# KamiGen2.net
KiCad netlist of a schematic drawn in Altium Designer
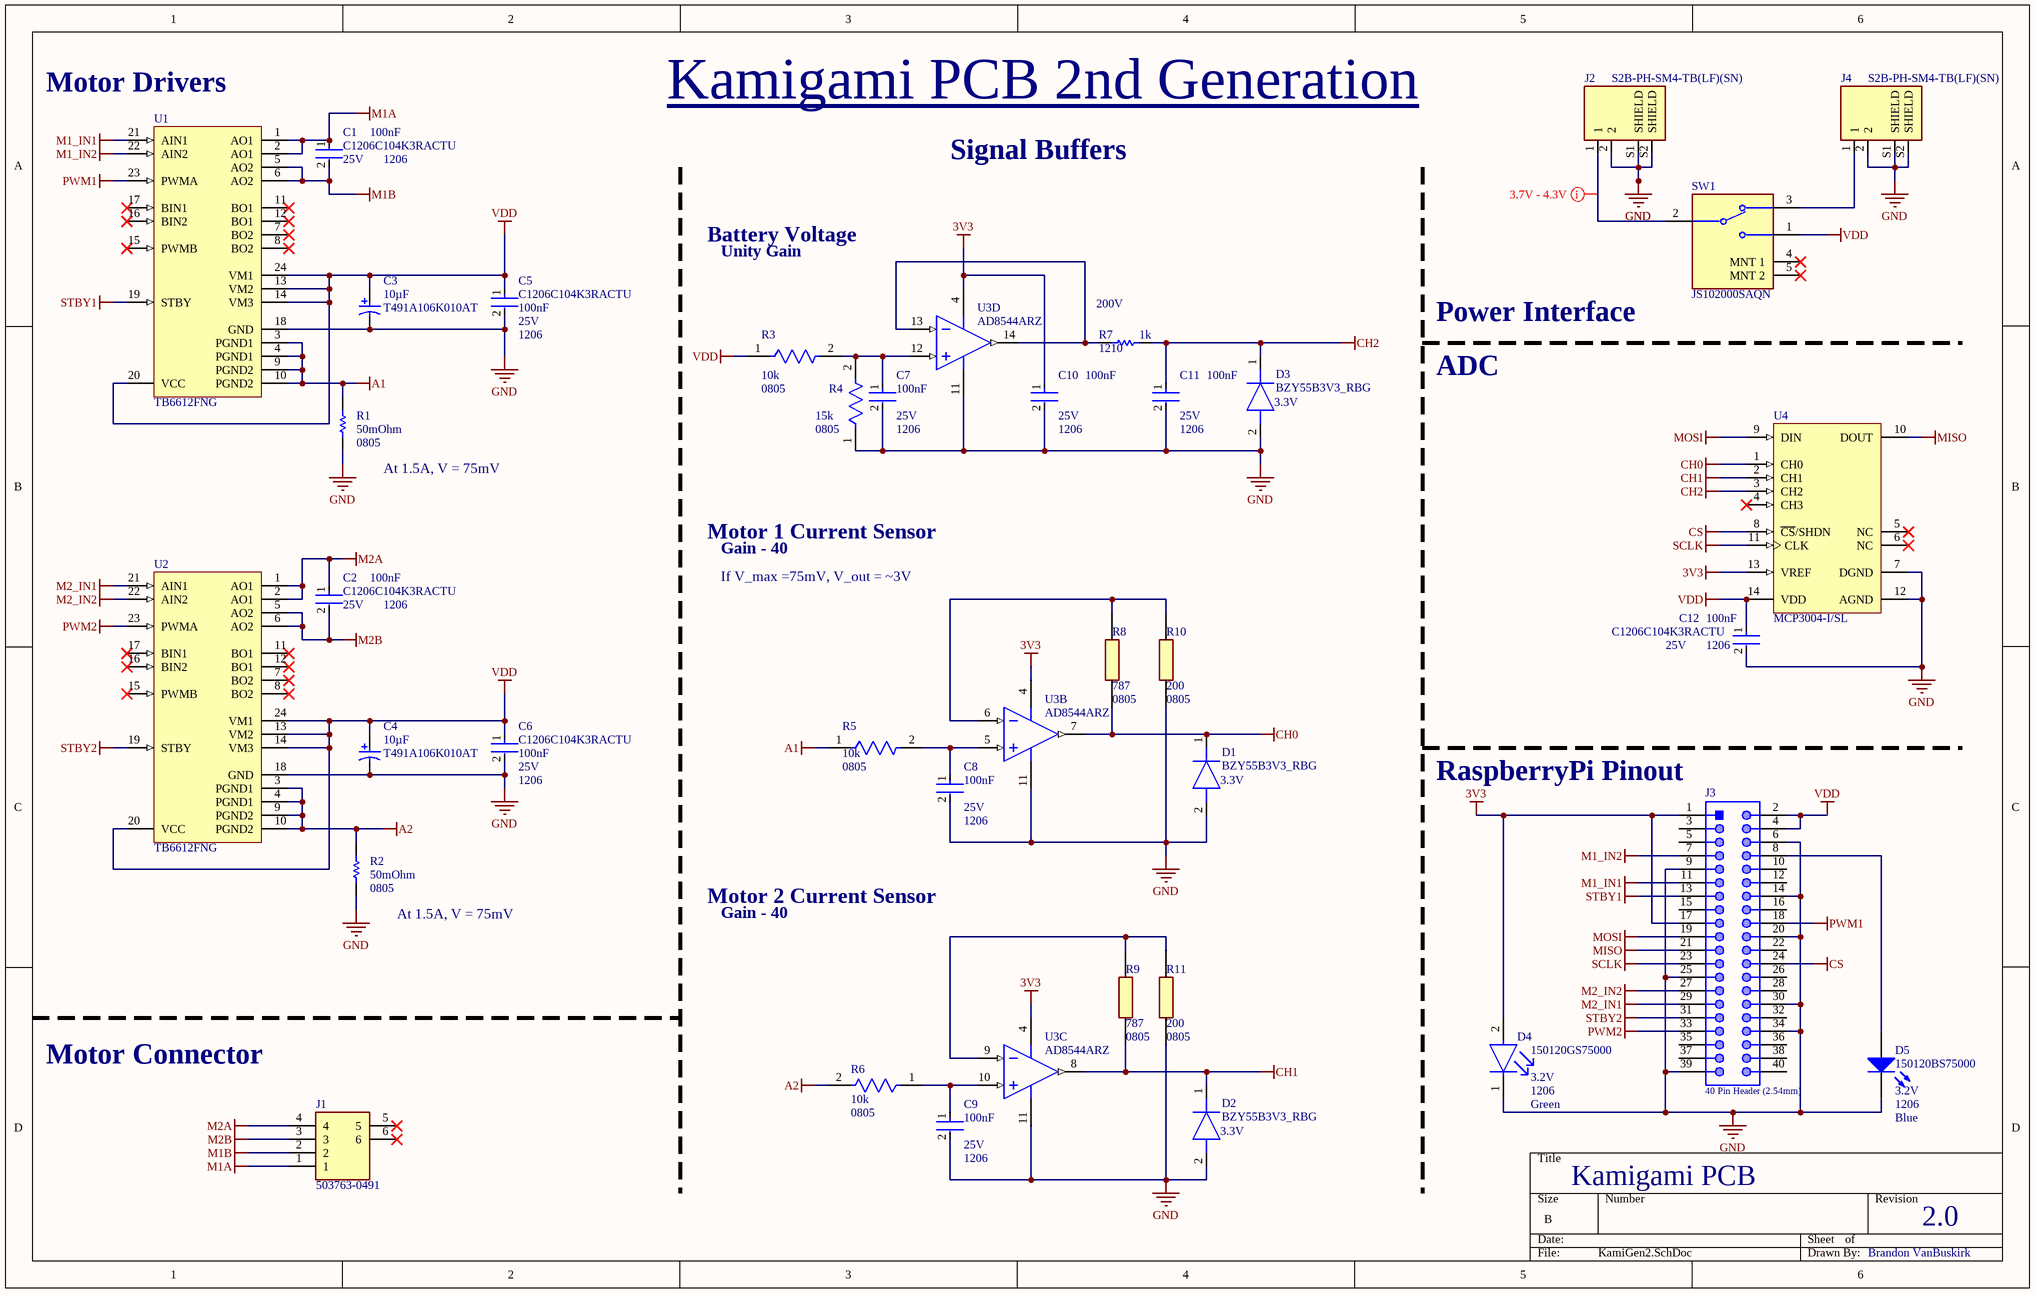
[diagram p0: KamiGen2.SchDoc]

(export (version "E")
  (design (tool "Eeschema 10.0.6"))
  (components
    (comp (ref "C1")
      (value "C1206C104K3RACTU")
      (footprint "FP-C1206C-EB-MFG")
      (description "CAP CER 0.1UF 25V 10% X7R 1206")
      (fields
        (field (name "ALTIUM_VALUE") "100nF")
        (field (name "VOLTAGE RATING (DC)") "25V")
        (field (name "TOLERANCE") "10%")
        (field (name "CASE CODE (IMPERIAL)") "1206")
      )
      (libsource (lib "Verdant Robotics") (part "b4654b650e69147ec39a6b967a45e02"))
    )
    (comp (ref "C2")
      (value "C1206C104K3RACTU")
      (footprint "FP-C1206C-EB-MFG")
      (description "CAP CER 0.1UF 25V 10% X7R 1206")
      (fields
        (field (name "ALTIUM_VALUE") "100nF")
        (field (name "VOLTAGE RATING (DC)") "25V")
        (field (name "TOLERANCE") "10%")
        (field (name "CASE CODE (IMPERIAL)") "1206")
      )
      (libsource (lib "Verdant Robotics") (part "b4654b650e69147ec39a6b967a45e02"))
    )
    (comp (ref "C3")
      (value "T491A106K010AT")
      (footprint "KEMT-A-3216-18-2_M")
      (description "Capacitor, Tantalum, 10 uF, +/- 10%, 10 V, -55 to 125 degC, 2-Pin SMD (1206), RoHS, Tape and Reel")
      (fields
        (field (name "TOLERANCE") "±10%")
        (field (name "MANUFACTURER") "Kemet")
        (field (name "CAPACITANCE") "10µF")
      )
      (libsource (lib "Altium Content Vault") (part "CAP-P-2"))
    )
    (comp (ref "C4")
      (value "T491A106K010AT")
      (footprint "KEMT-A-3216-18-2_M")
      (description "Capacitor, Tantalum, 10 uF, +/- 10%, 10 V, -55 to 125 degC, 2-Pin SMD (1206), RoHS, Tape and Reel")
      (fields
        (field (name "TOLERANCE") "±10%")
        (field (name "MANUFACTURER") "Kemet")
        (field (name "CAPACITANCE") "10µF")
      )
      (libsource (lib "Altium Content Vault") (part "CAP-P-2"))
    )
    (comp (ref "C5")
      (value "C1206C104K3RACTU")
      (footprint "FP-C1206C-EB-MFG")
      (description "CAP CER 0.1UF 25V 10% X7R 1206")
      (fields
        (field (name "ALTIUM_VALUE") "100nF")
        (field (name "VOLTAGE RATING (DC)") "25V")
        (field (name "TOLERANCE") "10%")
        (field (name "CASE CODE (IMPERIAL)") "1206")
      )
      (libsource (lib "Verdant Robotics") (part "b4654b650e69147ec39a6b967a45e02"))
    )
    (comp (ref "C6")
      (value "C1206C104K3RACTU")
      (footprint "FP-C1206C-EB-MFG")
      (description "CAP CER 0.1UF 25V 10% X7R 1206")
      (fields
        (field (name "ALTIUM_VALUE") "100nF")
        (field (name "VOLTAGE RATING (DC)") "25V")
        (field (name "TOLERANCE") "10%")
        (field (name "CASE CODE (IMPERIAL)") "1206")
      )
      (libsource (lib "Verdant Robotics") (part "b4654b650e69147ec39a6b967a45e02"))
    )
    (comp (ref "C7")
      (value "100nF")
      (footprint "FP-C1206C-EB-MFG")
      (description "CAP CER 0.1UF 25V 10% X7R 1206")
      (fields
        (field (name "VOLTAGE RATING (DC)") "25V")
        (field (name "TOLERANCE") "10%")
        (field (name "CASE CODE (IMPERIAL)") "1206")
        (field (name "Comment") "C1206C104K3RACTU")
      )
      (libsource (lib "Verdant Robotics") (part "b4654b650e69147ec39a6b967a45e02"))
    )
    (comp (ref "C8")
      (value "100nF")
      (footprint "FP-C1206C-EB-MFG")
      (description "CAP CER 0.1UF 25V 10% X7R 1206")
      (fields
        (field (name "VOLTAGE RATING (DC)") "25V")
        (field (name "TOLERANCE") "10%")
        (field (name "CASE CODE (IMPERIAL)") "1206")
        (field (name "Comment") "C1206C104K3RACTU")
      )
      (libsource (lib "Verdant Robotics") (part "b4654b650e69147ec39a6b967a45e02"))
    )
    (comp (ref "C9")
      (value "100nF")
      (footprint "FP-C1206C-EB-MFG")
      (description "CAP CER 0.1UF 25V 10% X7R 1206")
      (fields
        (field (name "VOLTAGE RATING (DC)") "25V")
        (field (name "TOLERANCE") "10%")
        (field (name "CASE CODE (IMPERIAL)") "1206")
        (field (name "Comment") "C1206C104K3RACTU")
      )
      (libsource (lib "Verdant Robotics") (part "b4654b650e69147ec39a6b967a45e02"))
    )
    (comp (ref "C10")
      (value "100nF")
      (footprint "FP-C1206C-EB-MFG")
      (description "CAP CER 0.1UF 25V 10% X7R 1206")
      (fields
        (field (name "VOLTAGE RATING (DC)") "25V")
        (field (name "TOLERANCE") "10%")
        (field (name "CASE CODE (IMPERIAL)") "1206")
        (field (name "Comment") "C1206C104K3RACTU")
      )
      (libsource (lib "Verdant Robotics") (part "b4654b650e69147ec39a6b967a45e02"))
    )
    (comp (ref "C11")
      (value "100nF")
      (footprint "FP-C1206C-EB-MFG")
      (description "CAP CER 0.1UF 25V 10% X7R 1206")
      (fields
        (field (name "VOLTAGE RATING (DC)") "25V")
        (field (name "TOLERANCE") "10%")
        (field (name "CASE CODE (IMPERIAL)") "1206")
        (field (name "Comment") "C1206C104K3RACTU")
      )
      (libsource (lib "Verdant Robotics") (part "b4654b650e69147ec39a6b967a45e02"))
    )
    (comp (ref "C12")
      (value "C1206C104K3RACTU")
      (footprint "FP-C1206C-EB-MFG")
      (description "CAP CER 0.1UF 25V 10% X7R 1206")
      (fields
        (field (name "ALTIUM_VALUE") "100nF")
        (field (name "VOLTAGE RATING (DC)") "25V")
        (field (name "TOLERANCE") "10%")
        (field (name "CASE CODE (IMPERIAL)") "1206")
      )
      (libsource (lib "Verdant Robotics") (part "b4654b650e69147ec39a6b967a45e02"))
    )
    (comp (ref "D1")
      (value "BZY55B3V3_RBG")
      (footprint "SamacSys:BZY55B3V3RBG")
      (description "Diode")
      (fields
        (field (name "MANUFACTURER_PART_NUMBER") "BZY55B3V3 RBG")
        (field (name "MOUSER PART NUMBER") "821-BZY55B3V3RBG")
        (field (name "ZENER VOLTAGE") "3.3V")
      )
      (libsource (lib "*") (part "BZY55B3V3_RBG"))
    )
    (comp (ref "D2")
      (value "BZY55B3V3_RBG")
      (footprint "SamacSys:BZY55B3V3RBG")
      (description "Diode")
      (fields
        (field (name "MANUFACTURER_PART_NUMBER") "BZY55B3V3 RBG")
        (field (name "MOUSER PART NUMBER") "821-BZY55B3V3RBG")
        (field (name "ZENER VOLTAGE") "3.3V")
      )
      (libsource (lib "*") (part "BZY55B3V3_RBG"))
    )
    (comp (ref "D3")
      (value "BZY55B3V3_RBG")
      (footprint "SamacSys:BZY55B3V3RBG")
      (description "Diode")
      (fields
        (field (name "MANUFACTURER_PART_NUMBER") "BZY55B3V3 RBG")
        (field (name "MOUSER PART NUMBER") "821-BZY55B3V3RBG")
        (field (name "ZENER VOLTAGE") "3.3V")
      )
      (libsource (lib "*") (part "BZY55B3V3_RBG"))
    )
    (comp (ref "D4")
      (value "150120GS75000")
      (footprint "FP-150120GS75000-MFG")
      (description "LED GREEN CLEAR 1206 SMD")
      (fields
        (field (name "COLOR") "Green")
        (field (name "CASE/PACKAGE") "1206")
        (field (name "FORWARD VOLTAGE") "3.2V")
      )
      (libsource (lib "Altium Content Vault") (part "8706943c75ba83719d021d2fdc84c58"))
    )
    (comp (ref "D5")
      (value "150120BS75000")
      (footprint "1206_A")
      (description "SMD mono-color Chip LED, WL-SMCW, Blue")
      (fields
        (field (name "MANUFACTURER") "Wuerth Elektronik")
        (field (name "PACKAGEREFERENCE") "1206")
        (field (name "COLOR") "Blue")
        (field (name "FORWARD VOLTAGE") "3.2V")
      )
      (libsource (lib "Altium Content Vault") (part "WE-LED_K1A2-2"))
    )
    (comp (ref "J1")
      (value "503763-0491")
      (footprint "SamacSys:5037630491")
      (description "Connector")
      (fields (field (name "MOUSER PART NUMBER") "538-503763-0491"))
      (libsource (lib "*") (part "503763-0491"))
    )
    (comp (ref "J2")
      (value "S2B-PH-SM4-TB(LF)(SN)")
      (footprint "JST_S2B-PH-SM4-TB(LF)(SN)")
      (description "Connector Header Surface Mount, Right Angle 2 position 0.079 (2.00mm)")
      (fields (field (name "DIGI-KEY_PART_NUMBER") "455-1749-2-ND") (field (name "MF") "JST Sales"))
      (libsource (lib "Verdant Robotics") (part "S2B-PH-SM4-TB(LF)(SN)"))
    )
    (comp (ref "J3")
      (value "40 Pin Header (2.54mm)")
      (footprint "61304021121")
      (description "WR-PHD Straight Male, PCB Header, Through Hole, 2 Rows, 40 Contacts, 2.54mm Pitch")
      (libsource (lib "Verdant Robotics") (part "WE-CN-2P-M-R40"))
    )
    (comp (ref "J4")
      (value "S2B-PH-SM4-TB(LF)(SN)")
      (footprint "JST_S2B-PH-SM4-TB(LF)(SN)")
      (description "Connector Header Surface Mount, Right Angle 2 position 0.079 (2.00mm)")
      (fields (field (name "DIGI-KEY_PART_NUMBER") "455-1749-2-ND") (field (name "MF") "JST Sales"))
      (libsource (lib "Verdant Robotics") (part "S2B-PH-SM4-TB(LF)(SN)"))
    )
    (comp (ref "R1")
      (value "WSL0805R0500FEA")
      (footprint "RESC2013X46X38ML25T25")
      (fields
        (field (name "MANUFACTURER") "Vishay Dale")
        (field (name "RESISTANCE") "50mOhm")
        (field (name "CASE") "0805")
      )
      (libsource (lib "Altium Content Vault") (part "RES"))
    )
    (comp (ref "R2")
      (value "WSL0805R0500FEA")
      (footprint "RESC2013X46X38ML25T25")
      (fields
        (field (name "MANUFACTURER") "Vishay Dale")
        (field (name "RESISTANCE") "50mOhm")
        (field (name "CASE") "0805")
      )
      (libsource (lib "Altium Content Vault") (part "RES"))
    )
    (comp (ref "R3")
      (value "CRCW080510K0FKEA")
      (footprint "FP-CRCW0805-e3-IPC_A")
      (description "RES Thick Film, 10kΩ, 1%, 0.125W, 100ppm/°C, 0805")
      (fields
        (field (name "RESISTANCE") "10k")
        (field (name "TOLERANCE") "1%")
        (field (name "CASE/PACKAGE") "0805")
      )
      (libsource (lib "Altium Content Vault") (part "1029c3af85768c4190bb7ad29bc67b5"))
    )
    (comp (ref "R4")
      (value "ERJ-6ENF1502V")
      (footprint "FP-ERJ6EN-IPC_C")
      (description "RES SMD 15K OHM 1% 1/8W 0805")
      (fields
        (field (name "CASE/PACKAGE") "0805")
        (field (name "TOLERANCE") "1%")
        (field (name "RESISTANCE") "15k")
      )
      (libsource (lib "Altium Content Vault") (part "8db39607336c341a927600551d01821"))
    )
    (comp (ref "R5")
      (value "CRCW080510K0FKEA")
      (footprint "FP-CRCW0805-e3-IPC_A")
      (description "RES Thick Film, 10kΩ, 1%, 0.125W, 100ppm/°C, 0805")
      (fields
        (field (name "RESISTANCE") "10k")
        (field (name "TOLERANCE") "1%")
        (field (name "CASE/PACKAGE") "0805")
      )
      (libsource (lib "Altium Content Vault") (part "1029c3af85768c4190bb7ad29bc67b5"))
    )
    (comp (ref "R6")
      (value "CRCW080510K0FKEA")
      (footprint "FP-CRCW0805-e3-IPC_A")
      (description "RES Thick Film, 10kΩ, 1%, 0.125W, 100ppm/°C, 0805")
      (fields
        (field (name "RESISTANCE") "10k")
        (field (name "TOLERANCE") "1%")
        (field (name "CASE/PACKAGE") "0805")
      )
      (libsource (lib "Altium Content Vault") (part "1029c3af85768c4190bb7ad29bc67b5"))
    )
    (comp (ref "R7")
      (value "1k")
      (footprint "RESC3225X70X50LL20T20")
      (description "Res Thick Film 1210 1K Ohm 1% 1/2W ±100ppm/°C Molded SMD Embossed Carrier T/R")
      (fields
        (field (name "CASE CODE (IMPERIAL)") "1210")
        (field (name "TOLERANCE") "1%")
        (field (name "VOLTAGE RATING (DC)") "200V")
        (field (name "Comment") "ERJ-14NF1001U")
      )
      (libsource (lib "Verdant Robotics") (part "RES"))
    )
    (comp (ref "R8")
      (value "CRGH0805F787R")
      (footprint "SamacSys:RESC2013X65N")
      (description "Resistor")
      (fields
        (field (name "MOUSER PART NUMBER") "279-CRGH0805F787R")
        (field (name "RESISTANCE") "787")
        (field (name "CASE") "0805")
      )
      (libsource (lib "*") (part "CRGH0805F787R"))
    )
    (comp (ref "R9")
      (value "CRGH0805F787R")
      (footprint "SamacSys:RESC2013X65N")
      (description "Resistor")
      (fields
        (field (name "MOUSER PART NUMBER") "279-CRGH0805F787R")
        (field (name "RESISTANCE") "787")
        (field (name "CASE") "0805")
      )
      (libsource (lib "*") (part "CRGH0805F787R"))
    )
    (comp (ref "R10")
      (value "ERJ-6RBD2000V")
      (footprint "SamacSys:RESC2012X70N")
      (description "Resistor")
      (fields
        (field (name "MOUSER PART NUMBER") "667-ERJ-6RBD2000V")
        (field (name "RESISTANCE") "200")
        (field (name "CASE") "0805")
      )
      (libsource (lib "*") (part "ERJ-6RBD2000V"))
    )
    (comp (ref "R11")
      (value "ERJ-6RBD2000V")
      (footprint "SamacSys:RESC2012X70N")
      (description "Resistor")
      (fields
        (field (name "MOUSER PART NUMBER") "667-ERJ-6RBD2000V")
        (field (name "RESISTANCE") "200")
        (field (name "CASE") "0805")
      )
      (libsource (lib "*") (part "ERJ-6RBD2000V"))
    )
    (comp (ref "SW1")
      (value "JS102000SAQN")
      (footprint "FP-JS102000SAQN-MFG")
      (description "Slide Switch, Js Series, SPDT, Right Angle, SMD, 1 ma Rohs Compliant: Yes")
      (libsource (lib "Verdant Robotics") (part "6887e5fe807d9c5c2853bed39bc55bf"))
    )
    (comp (ref "U1")
      (value "TB6612FNG")
      (footprint "TOSH-SSOP-24_M")
      (description "Driver IC for Dual DC Motor, 15 V, -20 to 85 degC, 24-Pin SSOP, RoHS, Tape and Reel")
      (libsource (lib "Altium Content Vault") (part "TOSH-TB6612FNG-SOP-24"))
    )
    (comp (ref "U2")
      (value "TB6612FNG")
      (footprint "TOSH-SSOP-24_M")
      (description "Driver IC for Dual DC Motor, 15 V, -20 to 85 degC, 24-Pin SSOP, RoHS, Tape and Reel")
      (libsource (lib "Altium Content Vault") (part "TOSH-TB6612FNG-SOP-24"))
    )
    (comp (ref "U3")
      (value "AD8544ARZ")
      (footprint "ADI-R-14_M")
      (description "Operational Amplifier, Quad, 1 Mhz, 4, 0.92 V/ S, 2.7V To 5.5V, Soic, 14 Rohs Compliant: Yes")
      (libsource (lib "Verdant Robotics") (part "ADI-ADxxxx_OPxxxx-X-14"))
    )
    (comp (ref "U4")
      (value "MCP3004-I/SL")
      (footprint "SOIC-SL14_L")
      (description "4-Channel Single ADC SAR 200ksps 10-bit Serial Automotive 14-Pin SOIC N Tube")
      (libsource (lib "Verdant Robotics") (part "CON-ADC-MCP3004-14"))
    )
  )
  (nets
    (net (code "1") (name "3V3") (class "Default")
      (node (ref "C10") (pin "1") (pinfunction "1_1") (pintype "passive"))
      (node (ref "D4") (pin "2") (pinfunction "A_2") (pintype "passive"))
      (node (ref "J3") (pin "1") (pinfunction "1_1") (pintype "passive"))
      (node (ref "J3") (pin "17") (pinfunction "17_17") (pintype "passive"))
      (node (ref "U3") (pin "4") (pinfunction "+V_4") (pintype "power_in"))
      (node (ref "U4") (pin "13") (pinfunction "VREF_13") (pintype "input"))
    )
    (net (code "2") (name "A1") (class "Default")
      (node (ref "R1") (pin "2") (pinfunction "2_2") (pintype "passive"))
      (node (ref "R5") (pin "1") (pinfunction "1_1") (pintype "passive"))
      (node (ref "U1") (pin "10") (pinfunction "PGND2_10") (pintype "power_in"))
      (node (ref "U1") (pin "3") (pinfunction "PGND1_3") (pintype "power_in"))
      (node (ref "U1") (pin "4") (pinfunction "PGND1_4") (pintype "power_in"))
      (node (ref "U1") (pin "9") (pinfunction "PGND2_9") (pintype "power_in"))
    )
    (net (code "3") (name "A2") (class "Default")
      (node (ref "R2") (pin "2") (pinfunction "2_2") (pintype "passive"))
      (node (ref "R6") (pin "2") (pinfunction "2_2") (pintype "passive"))
      (node (ref "U2") (pin "10") (pinfunction "PGND2_10") (pintype "power_in"))
      (node (ref "U2") (pin "3") (pinfunction "PGND1_3") (pintype "power_in"))
      (node (ref "U2") (pin "4") (pinfunction "PGND1_4") (pintype "power_in"))
      (node (ref "U2") (pin "9") (pinfunction "PGND2_9") (pintype "power_in"))
    )
    (net (code "4") (name "CH0") (class "Default")
      (node (ref "D1") (pin "1") (pinfunction "K_1") (pintype "passive"))
      (node (ref "R8") (pin "1") (pinfunction "1_1") (pintype "passive"))
      (node (ref "U3") (pin "7") (pinfunction "OUT_B_7") (pintype "output"))
      (node (ref "U4") (pin "1") (pinfunction "CH0_1") (pintype "input"))
    )
    (net (code "5") (name "CH1") (class "Default")
      (node (ref "D2") (pin "1") (pinfunction "K_1") (pintype "passive"))
      (node (ref "R9") (pin "1") (pinfunction "1_1") (pintype "passive"))
      (node (ref "U3") (pin "8") (pinfunction "OUT_C_8") (pintype "output"))
      (node (ref "U4") (pin "2") (pinfunction "CH1_2") (pintype "input"))
    )
    (net (code "6") (name "CH2") (class "Default")
      (node (ref "C11") (pin "1") (pinfunction "1_1") (pintype "passive"))
      (node (ref "D3") (pin "1") (pinfunction "K_1") (pintype "passive"))
      (node (ref "R7") (pin "2") (pinfunction "2_2") (pintype "passive"))
      (node (ref "U4") (pin "3") (pinfunction "CH2_3") (pintype "input"))
    )
    (net (code "7") (name "CS") (class "Default")
      (node (ref "J3") (pin "24") (pinfunction "24_24") (pintype "passive"))
      (node (ref "U4") (pin "8") (pinfunction "~{CS}/SHDN_8") (pintype "input"))
    )
    (net (code "8") (name "GND") (class "Default")
      (node (ref "C10") (pin "2") (pinfunction "2_2") (pintype "passive"))
      (node (ref "C11") (pin "2") (pinfunction "2_2") (pintype "passive"))
      (node (ref "C12") (pin "2") (pinfunction "2_2") (pintype "passive"))
      (node (ref "C3") (pin "2") (pinfunction "2_2") (pintype "passive"))
      (node (ref "C4") (pin "2") (pinfunction "2_2") (pintype "passive"))
      (node (ref "C5") (pin "2") (pinfunction "2_2") (pintype "passive"))
      (node (ref "C6") (pin "2") (pinfunction "2_2") (pintype "passive"))
      (node (ref "C7") (pin "2") (pinfunction "2_2") (pintype "passive"))
      (node (ref "C8") (pin "2") (pinfunction "2_2") (pintype "passive"))
      (node (ref "C9") (pin "2") (pinfunction "2_2") (pintype "passive"))
      (node (ref "D1") (pin "2") (pinfunction "A_2") (pintype "passive"))
      (node (ref "D2") (pin "2") (pinfunction "A_2") (pintype "passive"))
      (node (ref "D3") (pin "2") (pinfunction "A_2") (pintype "passive"))
      (node (ref "D4") (pin "1") (pinfunction "C_1") (pintype "passive"))
      (node (ref "D5") (pin "1") (pinfunction "K_1") (pintype "passive"))
      (node (ref "J2") (pin "2") (pinfunction "2_2") (pintype "passive"))
      (node (ref "J2") (pin "S1") (pinfunction "SHIELD_S1") (pintype "passive"))
      (node (ref "J2") (pin "S2") (pinfunction "SHIELD_S2") (pintype "passive"))
      (node (ref "J3") (pin "14") (pinfunction "14_14") (pintype "passive"))
      (node (ref "J3") (pin "20") (pinfunction "20_20") (pintype "passive"))
      (node (ref "J3") (pin "25") (pinfunction "25_25") (pintype "passive"))
      (node (ref "J3") (pin "30") (pinfunction "30_30") (pintype "passive"))
      (node (ref "J3") (pin "34") (pinfunction "34_34") (pintype "passive"))
      (node (ref "J3") (pin "39") (pinfunction "39_39") (pintype "passive"))
      (node (ref "J3") (pin "6") (pinfunction "6_6") (pintype "passive"))
      (node (ref "J3") (pin "9") (pinfunction "9_9") (pintype "passive"))
      (node (ref "J4") (pin "2") (pinfunction "2_2") (pintype "passive"))
      (node (ref "J4") (pin "S1") (pinfunction "SHIELD_S1") (pintype "passive"))
      (node (ref "J4") (pin "S2") (pinfunction "SHIELD_S2") (pintype "passive"))
      (node (ref "R1") (pin "1") (pinfunction "1_1") (pintype "passive"))
      (node (ref "R10") (pin "1") (pinfunction "1_1") (pintype "passive"))
      (node (ref "R11") (pin "1") (pinfunction "1_1") (pintype "passive"))
      (node (ref "R2") (pin "1") (pinfunction "1_1") (pintype "passive"))
      (node (ref "R4") (pin "1") (pinfunction "1_1") (pintype "passive"))
      (node (ref "U1") (pin "18") (pinfunction "GND_18") (pintype "power_in"))
      (node (ref "U2") (pin "18") (pinfunction "GND_18") (pintype "power_in"))
      (node (ref "U3") (pin "11") (pinfunction "-V_11") (pintype "power_in"))
      (node (ref "U4") (pin "12") (pinfunction "AGND_12") (pintype "power_in"))
      (node (ref "U4") (pin "7") (pinfunction "DGND_7") (pintype "power_in"))
    )
    (net (code "9") (name "M1A") (class "Default")
      (node (ref "C1") (pin "1") (pinfunction "1_1") (pintype "passive"))
      (node (ref "J1") (pin "1") (pinfunction "1_1") (pintype "passive"))
      (node (ref "U1") (pin "1") (pinfunction "AO1_1") (pintype "tri_state"))
      (node (ref "U1") (pin "2") (pinfunction "AO1_2") (pintype "tri_state"))
    )
    (net (code "10") (name "M1B") (class "Default")
      (node (ref "C1") (pin "2") (pinfunction "2_2") (pintype "passive"))
      (node (ref "J1") (pin "2") (pinfunction "2_2") (pintype "passive"))
      (node (ref "U1") (pin "5") (pinfunction "AO2_5") (pintype "tri_state"))
      (node (ref "U1") (pin "6") (pinfunction "AO2_6") (pintype "tri_state"))
    )
    (net (code "11") (name "M1_IN1") (class "Default")
      (node (ref "J3") (pin "11") (pinfunction "11_11") (pintype "passive"))
      (node (ref "U1") (pin "21") (pinfunction "AIN1_21") (pintype "input"))
    )
    (net (code "12") (name "M1_IN2") (class "Default")
      (node (ref "J3") (pin "7") (pinfunction "7_7") (pintype "passive"))
      (node (ref "U1") (pin "22") (pinfunction "AIN2_22") (pintype "input"))
    )
    (net (code "13") (name "M2A") (class "Default")
      (node (ref "C2") (pin "1") (pinfunction "1_1") (pintype "passive"))
      (node (ref "J1") (pin "4") (pinfunction "4_4") (pintype "passive"))
      (node (ref "U2") (pin "1") (pinfunction "AO1_1") (pintype "tri_state"))
      (node (ref "U2") (pin "2") (pinfunction "AO1_2") (pintype "tri_state"))
    )
    (net (code "14") (name "M2B") (class "Default")
      (node (ref "C2") (pin "2") (pinfunction "2_2") (pintype "passive"))
      (node (ref "J1") (pin "3") (pinfunction "3_3") (pintype "passive"))
      (node (ref "U2") (pin "5") (pinfunction "AO2_5") (pintype "tri_state"))
      (node (ref "U2") (pin "6") (pinfunction "AO2_6") (pintype "tri_state"))
    )
    (net (code "15") (name "M2_IN1") (class "Default")
      (node (ref "J3") (pin "29") (pinfunction "29_29") (pintype "passive"))
      (node (ref "U2") (pin "21") (pinfunction "AIN1_21") (pintype "input"))
    )
    (net (code "16") (name "M2_IN2") (class "Default")
      (node (ref "J3") (pin "27") (pinfunction "27_27") (pintype "passive"))
      (node (ref "U2") (pin "22") (pinfunction "AIN2_22") (pintype "input"))
    )
    (net (code "17") (name "MISO") (class "Default")
      (node (ref "J3") (pin "21") (pinfunction "21_21") (pintype "passive"))
      (node (ref "U4") (pin "10") (pinfunction "DOUT_10") (pintype "tri_state"))
    )
    (net (code "18") (name "MOSI") (class "Default")
      (node (ref "J3") (pin "19") (pinfunction "19_19") (pintype "passive"))
      (node (ref "U4") (pin "9") (pinfunction "DIN_9") (pintype "input"))
    )
    (net (code "19") (name "Net-(D5-A)") (class "Default")
      (node (ref "D5") (pin "2") (pinfunction "A_2") (pintype "passive"))
      (node (ref "J3") (pin "8") (pinfunction "8_8") (pintype "passive"))
    )
    (net (code "20") (name "Net-(J4-Pad1)") (class "Default")
      (node (ref "J4") (pin "1") (pinfunction "1_1") (pintype "passive"))
      (node (ref "SW1") (pin "3") (pinfunction "3_3") (pintype "passive"))
    )
    (net (code "21") (name "Net-(SW1-C)") (class "Default")
      (node (ref "J2") (pin "1") (pinfunction "1_1") (pintype "passive"))
      (node (ref "SW1") (pin "2") (pinfunction "C_2") (pintype "passive"))
    )
    (net (code "22") (name "Net-(U3B-+IN_B)") (class "Default")
      (node (ref "C8") (pin "1") (pinfunction "1_1") (pintype "passive"))
      (node (ref "R5") (pin "2") (pinfunction "2_2") (pintype "passive"))
      (node (ref "U3") (pin "5") (pinfunction "+IN_B_5") (pintype "input"))
    )
    (net (code "23") (name "Net-(U3B--IN_B)") (class "Default")
      (node (ref "R10") (pin "2") (pinfunction "2_2") (pintype "passive"))
      (node (ref "R8") (pin "2") (pinfunction "2_2") (pintype "passive"))
      (node (ref "U3") (pin "6") (pinfunction "-IN_B_6") (pintype "input"))
    )
    (net (code "24") (name "Net-(U3C-+IN_C)") (class "Default")
      (node (ref "C9") (pin "1") (pinfunction "1_1") (pintype "passive"))
      (node (ref "R6") (pin "1") (pinfunction "1_1") (pintype "passive"))
      (node (ref "U3") (pin "10") (pinfunction "+IN_C_10") (pintype "input"))
    )
    (net (code "25") (name "Net-(U3C--IN_C)") (class "Default")
      (node (ref "R11") (pin "2") (pinfunction "2_2") (pintype "passive"))
      (node (ref "R9") (pin "2") (pinfunction "2_2") (pintype "passive"))
      (node (ref "U3") (pin "9") (pinfunction "-IN_C_9") (pintype "input"))
    )
    (net (code "26") (name "Net-(U3D-+IN_D)") (class "Default")
      (node (ref "C7") (pin "1") (pinfunction "1_1") (pintype "passive"))
      (node (ref "R3") (pin "2") (pinfunction "2_2") (pintype "passive"))
      (node (ref "R4") (pin "2") (pinfunction "2_2") (pintype "passive"))
      (node (ref "U3") (pin "12") (pinfunction "+IN_D_12") (pintype "input"))
    )
    (net (code "27") (name "Net-(U3D--IN_D)") (class "Default")
      (node (ref "R7") (pin "1") (pinfunction "1_1") (pintype "passive"))
      (node (ref "U3") (pin "13") (pinfunction "-IN_D_13") (pintype "input"))
      (node (ref "U3") (pin "14") (pinfunction "OUT_D_14") (pintype "output"))
    )
    (net (code "28") (name "PWM1") (class "Default")
      (node (ref "J3") (pin "18") (pinfunction "18_18") (pintype "passive"))
      (node (ref "U1") (pin "23") (pinfunction "PWMA_23") (pintype "input"))
    )
    (net (code "29") (name "PWM2") (class "Default")
      (node (ref "J3") (pin "33") (pinfunction "33_33") (pintype "passive"))
      (node (ref "U2") (pin "23") (pinfunction "PWMA_23") (pintype "input"))
    )
    (net (code "30") (name "SCLK") (class "Default")
      (node (ref "J3") (pin "23") (pinfunction "23_23") (pintype "passive"))
      (node (ref "U4") (pin "11") (pinfunction "CLK_11") (pintype "input"))
    )
    (net (code "31") (name "STBY1") (class "Default")
      (node (ref "J3") (pin "13") (pinfunction "13_13") (pintype "passive"))
      (node (ref "U1") (pin "19") (pinfunction "STBY_19") (pintype "input"))
    )
    (net (code "32") (name "STBY2") (class "Default")
      (node (ref "J3") (pin "31") (pinfunction "31_31") (pintype "passive"))
      (node (ref "U2") (pin "19") (pinfunction "STBY_19") (pintype "input"))
    )
    (net (code "33") (name "VDD") (class "Default")
      (node (ref "C12") (pin "1") (pinfunction "1_1") (pintype "passive"))
      (node (ref "C3") (pin "1") (pinfunction "1_1") (pintype "passive"))
      (node (ref "C4") (pin "1") (pinfunction "1_1") (pintype "passive"))
      (node (ref "C5") (pin "1") (pinfunction "1_1") (pintype "passive"))
      (node (ref "C6") (pin "1") (pinfunction "1_1") (pintype "passive"))
      (node (ref "J3") (pin "2") (pinfunction "2_2") (pintype "passive"))
      (node (ref "J3") (pin "4") (pinfunction "4_4") (pintype "passive"))
      (node (ref "R3") (pin "1") (pinfunction "1_1") (pintype "passive"))
      (node (ref "SW1") (pin "1") (pinfunction "1_1") (pintype "passive"))
      (node (ref "U1") (pin "13") (pinfunction "VM2_13") (pintype "power_in"))
      (node (ref "U1") (pin "14") (pinfunction "VM3_14") (pintype "power_in"))
      (node (ref "U1") (pin "20") (pinfunction "VCC_20") (pintype "power_in"))
      (node (ref "U1") (pin "24") (pinfunction "VM1_24") (pintype "power_in"))
      (node (ref "U2") (pin "13") (pinfunction "VM2_13") (pintype "power_in"))
      (node (ref "U2") (pin "14") (pinfunction "VM3_14") (pintype "power_in"))
      (node (ref "U2") (pin "20") (pinfunction "VCC_20") (pintype "power_in"))
      (node (ref "U2") (pin "24") (pinfunction "VM1_24") (pintype "power_in"))
      (node (ref "U4") (pin "14") (pinfunction "VDD_14") (pintype "power_in"))
    )
    (net (code "34") (name "unconnected-(J1-Pad5)") (class "Default")
      (node (ref "J1") (pin "5") (pinfunction "5_5") (pintype "passive+no_connect"))
    )
    (net (code "35") (name "unconnected-(J1-Pad6)") (class "Default")
      (node (ref "J1") (pin "6") (pinfunction "6_6") (pintype "passive+no_connect"))
    )
    (net (code "36") (name "unconnected-(J3-Pad3)") (class "Default")
      (node (ref "J3") (pin "3") (pinfunction "3_3") (pintype "passive"))
    )
    (net (code "37") (name "unconnected-(J3-Pad5)") (class "Default")
      (node (ref "J3") (pin "5") (pinfunction "5_5") (pintype "passive"))
    )
    (net (code "38") (name "unconnected-(J3-Pad10)") (class "Default")
      (node (ref "J3") (pin "10") (pinfunction "10_10") (pintype "passive"))
    )
    (net (code "39") (name "unconnected-(J3-Pad12)") (class "Default")
      (node (ref "J3") (pin "12") (pinfunction "12_12") (pintype "passive"))
    )
    (net (code "40") (name "unconnected-(J3-Pad15)") (class "Default")
      (node (ref "J3") (pin "15") (pinfunction "15_15") (pintype "passive"))
    )
    (net (code "41") (name "unconnected-(J3-Pad16)") (class "Default")
      (node (ref "J3") (pin "16") (pinfunction "16_16") (pintype "passive"))
    )
    (net (code "42") (name "unconnected-(J3-Pad22)") (class "Default")
      (node (ref "J3") (pin "22") (pinfunction "22_22") (pintype "passive"))
    )
    (net (code "43") (name "unconnected-(J3-Pad26)") (class "Default")
      (node (ref "J3") (pin "26") (pinfunction "26_26") (pintype "passive"))
    )
    (net (code "44") (name "unconnected-(J3-Pad28)") (class "Default")
      (node (ref "J3") (pin "28") (pinfunction "28_28") (pintype "passive"))
    )
    (net (code "45") (name "unconnected-(J3-Pad32)") (class "Default")
      (node (ref "J3") (pin "32") (pinfunction "32_32") (pintype "passive"))
    )
    (net (code "46") (name "unconnected-(J3-Pad35)") (class "Default")
      (node (ref "J3") (pin "35") (pinfunction "35_35") (pintype "passive"))
    )
    (net (code "47") (name "unconnected-(J3-Pad36)") (class "Default")
      (node (ref "J3") (pin "36") (pinfunction "36_36") (pintype "passive"))
    )
    (net (code "48") (name "unconnected-(J3-Pad37)") (class "Default")
      (node (ref "J3") (pin "37") (pinfunction "37_37") (pintype "passive"))
    )
    (net (code "49") (name "unconnected-(J3-Pad38)") (class "Default")
      (node (ref "J3") (pin "38") (pinfunction "38_38") (pintype "passive"))
    )
    (net (code "50") (name "unconnected-(J3-Pad40)") (class "Default")
      (node (ref "J3") (pin "40") (pinfunction "40_40") (pintype "passive"))
    )
    (net (code "51") (name "unconnected-(SW1-MNT_1-Pad4)") (class "Default")
      (node (ref "SW1") (pin "4") (pinfunction "MNT_1_4") (pintype "passive+no_connect"))
    )
    (net (code "52") (name "unconnected-(SW1-MNT_2-Pad5)") (class "Default")
      (node (ref "SW1") (pin "5") (pinfunction "MNT_2_5") (pintype "passive+no_connect"))
    )
    (net (code "53") (name "unconnected-(U1-BIN1-Pad17)") (class "Default")
      (node (ref "U1") (pin "17") (pinfunction "BIN1_17") (pintype "input+no_connect"))
    )
    (net (code "54") (name "unconnected-(U1-BIN2-Pad16)") (class "Default")
      (node (ref "U1") (pin "16") (pinfunction "BIN2_16") (pintype "input+no_connect"))
    )
    (net (code "55") (name "unconnected-(U1-BO1-Pad11)") (class "Default")
      (node (ref "U1") (pin "11") (pinfunction "BO1_11") (pintype "tri_state+no_connect"))
    )
    (net (code "56") (name "unconnected-(U1-BO1-Pad12)") (class "Default")
      (node (ref "U1") (pin "12") (pinfunction "BO1_12") (pintype "tri_state+no_connect"))
    )
    (net (code "57") (name "unconnected-(U1-BO2-Pad7)") (class "Default")
      (node (ref "U1") (pin "7") (pinfunction "BO2_7") (pintype "tri_state+no_connect"))
    )
    (net (code "58") (name "unconnected-(U1-BO2-Pad8)") (class "Default")
      (node (ref "U1") (pin "8") (pinfunction "BO2_8") (pintype "tri_state+no_connect"))
    )
    (net (code "59") (name "unconnected-(U1-PWMB-Pad15)") (class "Default")
      (node (ref "U1") (pin "15") (pinfunction "PWMB_15") (pintype "input+no_connect"))
    )
    (net (code "60") (name "unconnected-(U2-BIN1-Pad17)") (class "Default")
      (node (ref "U2") (pin "17") (pinfunction "BIN1_17") (pintype "input+no_connect"))
    )
    (net (code "61") (name "unconnected-(U2-BIN2-Pad16)") (class "Default")
      (node (ref "U2") (pin "16") (pinfunction "BIN2_16") (pintype "input+no_connect"))
    )
    (net (code "62") (name "unconnected-(U2-BO1-Pad11)") (class "Default")
      (node (ref "U2") (pin "11") (pinfunction "BO1_11") (pintype "tri_state+no_connect"))
    )
    (net (code "63") (name "unconnected-(U2-BO1-Pad12)") (class "Default")
      (node (ref "U2") (pin "12") (pinfunction "BO1_12") (pintype "tri_state+no_connect"))
    )
    (net (code "64") (name "unconnected-(U2-BO2-Pad7)") (class "Default")
      (node (ref "U2") (pin "7") (pinfunction "BO2_7") (pintype "tri_state+no_connect"))
    )
    (net (code "65") (name "unconnected-(U2-BO2-Pad8)") (class "Default")
      (node (ref "U2") (pin "8") (pinfunction "BO2_8") (pintype "tri_state+no_connect"))
    )
    (net (code "66") (name "unconnected-(U2-PWMB-Pad15)") (class "Default")
      (node (ref "U2") (pin "15") (pinfunction "PWMB_15") (pintype "input+no_connect"))
    )
    (net (code "67") (name "unconnected-(U4-CH3-Pad4)") (class "Default")
      (node (ref "U4") (pin "4") (pinfunction "CH3_4") (pintype "input+no_connect"))
    )
    (net (code "68") (name "unconnected-(U4-NC-Pad5)") (class "Default")
      (node (ref "U4") (pin "5") (pinfunction "NC_5") (pintype "passive+no_connect"))
    )
    (net (code "69") (name "unconnected-(U4-NC-Pad6)") (class "Default")
      (node (ref "U4") (pin "6") (pinfunction "NC_6") (pintype "passive+no_connect"))
    )
  )
)
